# BluetoothModule.net
KiCad netlist of a schematic drawn in Altium Designer
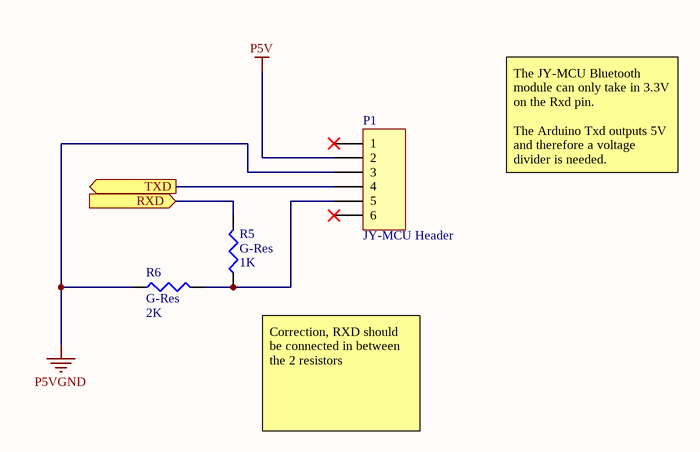
[diagram p0: BluetoothModule.SchDoc]

(export (version "E")
  (design (tool "Eeschema 10.0.6"))
  (components
    (comp (ref "P1")
      (value "JY-MCU Header")
      (footprint "HDR1X6_LGE1.0")
      (description "Header, 6-Pin")
      (fields (field (name "PUBLISHER") "Altium Limited"))
      (libsource (lib "PartsDatabaseV13p4") (part "C-Hdr1x6"))
    )
    (comp (ref "R5")
      (value "G-Res")
      (footprint "Res2.54mm_LGE1.0")
      (description "resistor (specify value)")
      (fields (field (name "ALTIUM_VALUE") "1K") (field (name "PUBLISHER") "Altium Limited"))
      (libsource (lib "PartsDatabaseV13p4") (part "G-Res"))
    )
    (comp (ref "R6")
      (value "G-Res")
      (footprint "Res2.54mm_LGE1.0")
      (description "resistor (specify value)")
      (fields (field (name "ALTIUM_VALUE") "2K") (field (name "PUBLISHER") "Altium Limited"))
      (libsource (lib "PartsDatabaseV13p4") (part "G-Res"))
    )
  )
  (nets
    (net (code "1") (name "/RXD") (class "Default")
      (node (ref "R5") (pin "2") (pinfunction "2_2") (pintype "passive"))
    )
    (net (code "2") (name "/TXD") (class "Default")
      (node (ref "P1") (pin "4") (pinfunction "4_4") (pintype "passive"))
    )
    (net (code "3") (name "Net-(P1-Pad5)") (class "Default")
      (node (ref "P1") (pin "5") (pinfunction "5_5") (pintype "passive"))
      (node (ref "R5") (pin "1") (pinfunction "1_1") (pintype "passive"))
      (node (ref "R6") (pin "2") (pinfunction "2_2") (pintype "passive"))
    )
    (net (code "4") (name "P5V") (class "Default")
      (node (ref "P1") (pin "2") (pinfunction "2_2") (pintype "passive"))
    )
    (net (code "5") (name "P5VGND") (class "Default")
      (node (ref "P1") (pin "3") (pinfunction "3_3") (pintype "passive"))
      (node (ref "R6") (pin "1") (pinfunction "1_1") (pintype "passive"))
    )
    (net (code "6") (name "unconnected-(P1-Pad1)") (class "Default")
      (node (ref "P1") (pin "1") (pinfunction "1_1") (pintype "passive+no_connect"))
    )
    (net (code "7") (name "unconnected-(P1-Pad6)") (class "Default")
      (node (ref "P1") (pin "6") (pinfunction "6_6") (pintype "passive+no_connect"))
    )
  )
)
